# hs-32-spi.net
KiCad netlist of a schematic drawn in EAGLE
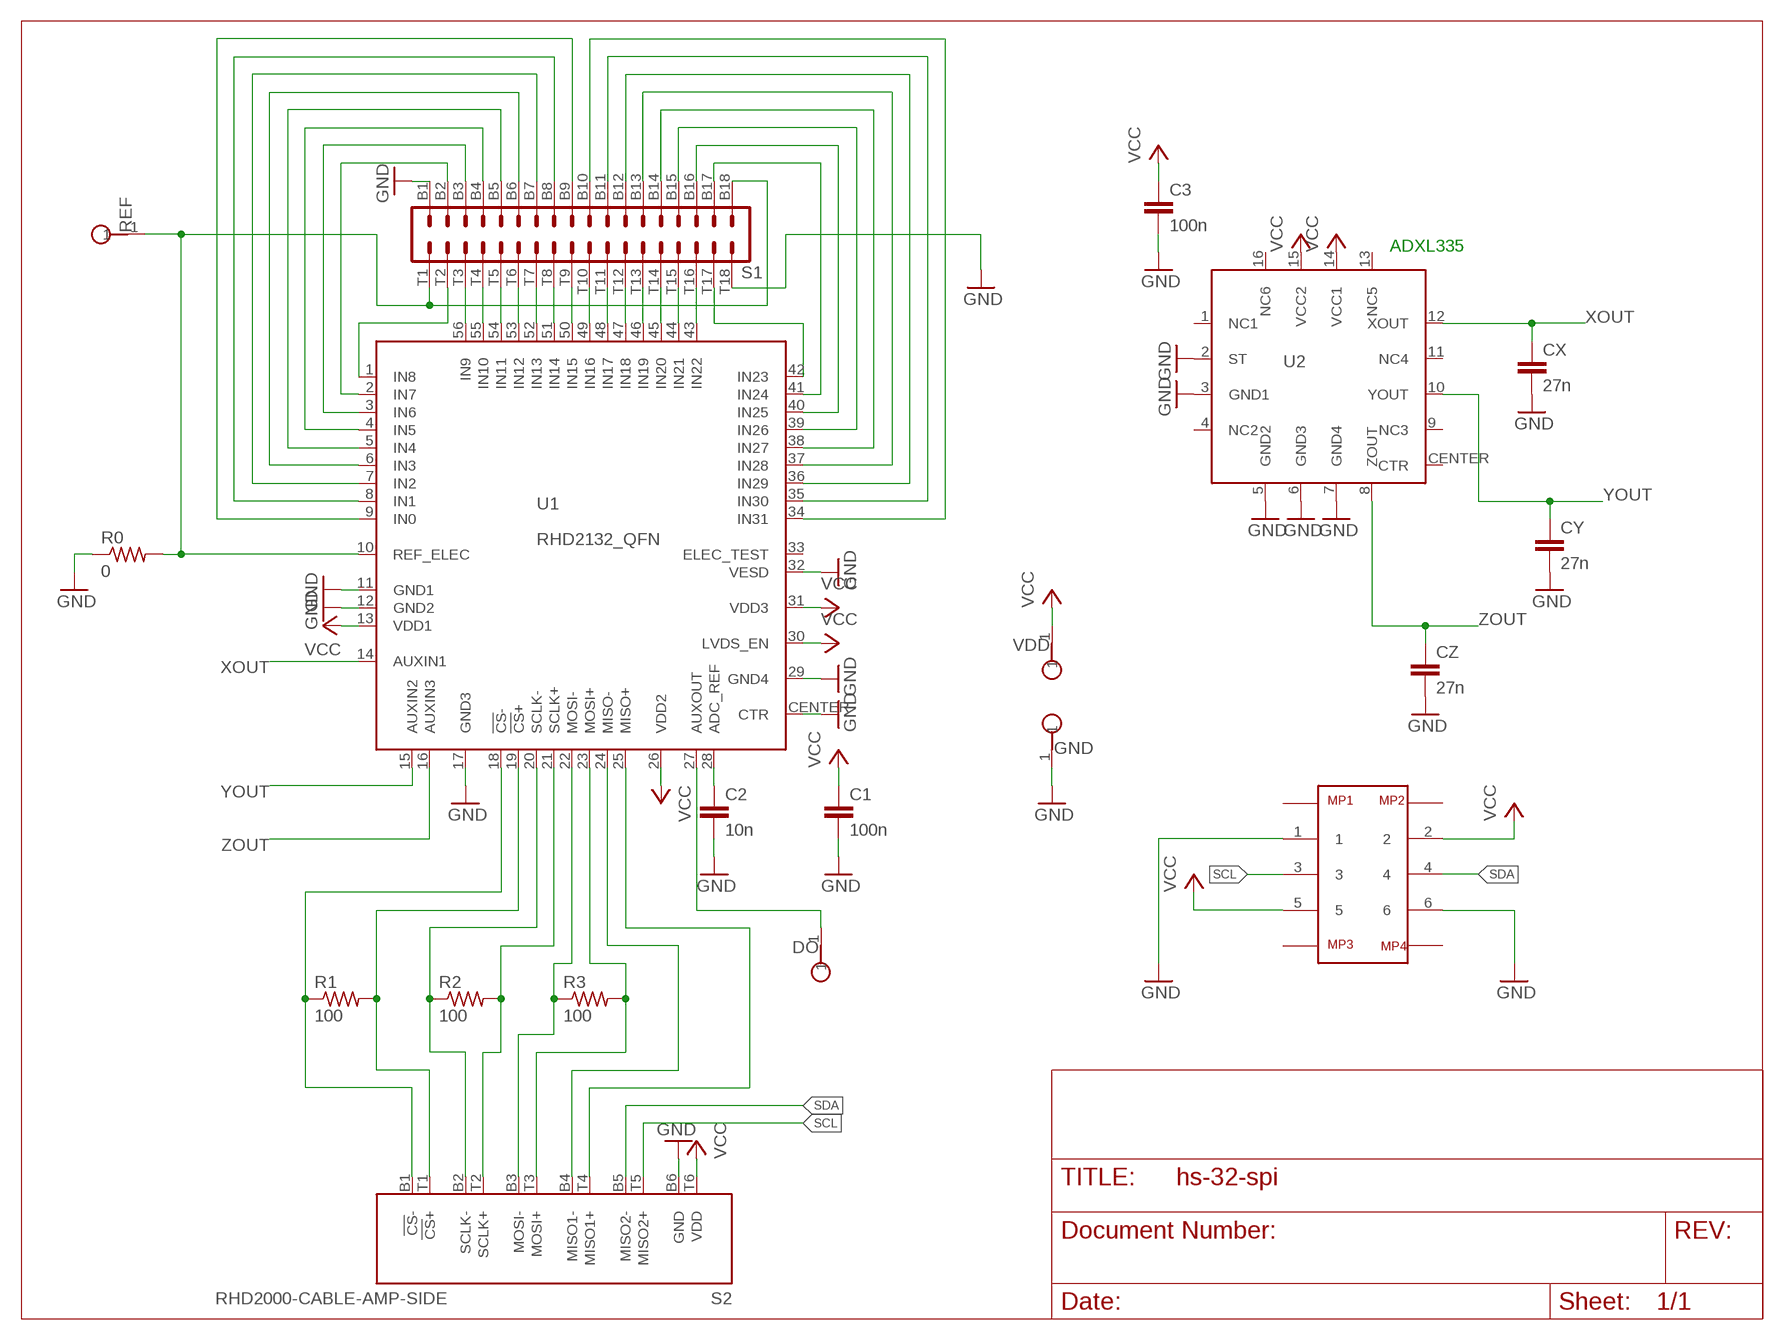
[diagram p0: schematic, sheet 1]

(export (version "E")
  (design (tool "Eeschema 10.0.6"))
  (components
    (comp (ref "C1")
      (value "100n")
      (footprint "eagle-import:0402")
      (libsource (lib "eagle-import") (part "C_0402"))
    )
    (comp (ref "C2")
      (value "10n")
      (footprint "eagle-import:0402")
      (libsource (lib "eagle-import") (part "C_0402"))
    )
    (comp (ref "C3")
      (value "100n")
      (footprint "eagle-import:0402")
      (libsource (lib "eagle-import") (part "C_0402"))
    )
    (comp (ref "CX")
      (value "27n")
      (footprint "eagle-import:0402")
      (libsource (lib "eagle-import") (part "C_0402"))
    )
    (comp (ref "CY")
      (value "27n")
      (footprint "eagle-import:0402")
      (libsource (lib "eagle-import") (part "C_0402"))
    )
    (comp (ref "CZ")
      (value "27n")
      (footprint "eagle-import:0402")
      (libsource (lib "eagle-import") (part "C_0402"))
    )
    (comp (ref "DO")
      (value "TESTPOINT_SMALL")
      (footprint "eagle-import:TESTPOINT_SMALL")
      (libsource (lib "eagle-import") (part "TESTPOINT_SMALL"))
    )
    (comp (ref "GND")
      (value "TESTPOINT_SMALL")
      (footprint "eagle-import:TESTPOINT_SMALL")
      (libsource (lib "eagle-import") (part "TESTPOINT_SMALL"))
    )
    (comp (ref "R0")
      (value "0")
      (footprint "eagle-import:0402")
      (libsource (lib "eagle-import") (part "R_0402"))
    )
    (comp (ref "R1")
      (value "100")
      (footprint "eagle-import:0201")
      (libsource (lib "eagle-import") (part "R_0201"))
    )
    (comp (ref "R2")
      (value "100")
      (footprint "eagle-import:0201")
      (libsource (lib "eagle-import") (part "R_0201"))
    )
    (comp (ref "R3")
      (value "100")
      (footprint "eagle-import:0201")
      (libsource (lib "eagle-import") (part "R_0201"))
    )
    (comp (ref "REF")
      (value "TESTPOINT_SMALL")
      (footprint "eagle-import:TESTPOINT_SMALL")
      (libsource (lib "eagle-import") (part "TESTPOINT_SMALL"))
    )
    (comp (ref "S1")
      (value "OMNETICS_A79025")
      (footprint "eagle-import:OMNETICS_A79025")
      (libsource (lib "eagle-import") (part "OMNETICS_A79025"))
    )
    (comp (ref "S2")
      (value "RHD2000-CABLE-AMP-SIDE")
      (footprint "eagle-import:OMNETICS_PZN-12-AA")
      (libsource (lib "eagle-import") (part "RHD2000-CABLE-AMP-SIDE"))
    )
    (comp (ref "U1")
      (value "RHD2132_QFN")
      (footprint "eagle-import:QFN56_8_X_8_LARGE")
      (libsource (lib "eagle-import") (part "RHD2132_QFN"))
    )
    (comp (ref "U2")
      (value "ADXL335")
      (footprint "eagle-import:ADXL335")
      (libsource (lib "eagle-import") (part "ADXL335"))
    )
    (comp (ref "U3")
      (value "MOLEX_5050700622")
      (footprint "eagle-import:MOLEX_5050700622")
      (libsource (lib "eagle-import") (part "MOLEX_5050700622"))
    )
    (comp (ref "VDD")
      (value "TESTPOINT_SMALL")
      (footprint "eagle-import:TESTPOINT_SMALL")
      (libsource (lib "eagle-import") (part "TESTPOINT_SMALL"))
    )
  )
  (nets
    (net (code "1") (name "/XOUT") (class "Default")
      (node (ref "CX") (pin "1") (pinfunction "1_1") (pintype "passive"))
      (node (ref "U1") (pin "14") (pinfunction "AUXIN1_14") (pintype "input"))
      (node (ref "U2") (pin "12") (pinfunction "XOUT_12") (pintype "output"))
    )
    (net (code "2") (name "/YOUT") (class "Default")
      (node (ref "CY") (pin "1") (pinfunction "1_1") (pintype "passive"))
      (node (ref "U1") (pin "15") (pinfunction "AUXIN2_15") (pintype "input"))
      (node (ref "U2") (pin "10") (pinfunction "YOUT_10") (pintype "output"))
    )
    (net (code "3") (name "/ZOUT") (class "Default")
      (node (ref "CZ") (pin "1") (pinfunction "1_1") (pintype "passive"))
      (node (ref "U1") (pin "16") (pinfunction "AUXIN3_16") (pintype "input"))
      (node (ref "U2") (pin "8") (pinfunction "ZOUT_8") (pintype "output"))
    )
    (net (code "4") (name "GND") (class "Default")
      (node (ref "C1") (pin "2") (pinfunction "2_2") (pintype "passive"))
      (node (ref "C2") (pin "2") (pinfunction "2_2") (pintype "passive"))
      (node (ref "C3") (pin "2") (pinfunction "2_2") (pintype "passive"))
      (node (ref "CX") (pin "2") (pinfunction "2_2") (pintype "passive"))
      (node (ref "CY") (pin "2") (pinfunction "2_2") (pintype "passive"))
      (node (ref "CZ") (pin "2") (pinfunction "2_2") (pintype "passive"))
      (node (ref "GND") (pin "1") (pinfunction "1_1") (pintype "passive"))
      (node (ref "R0") (pin "1") (pinfunction "1_1") (pintype "passive"))
      (node (ref "S1") (pin "B1") (pinfunction "B1_B1") (pintype "passive"))
      (node (ref "S1") (pin "T18") (pinfunction "T18_T18") (pintype "passive"))
      (node (ref "S2") (pin "B6") (pinfunction "GND_B6") (pintype "power_in"))
      (node (ref "U1") (pin "11") (pinfunction "GND1_11") (pintype "power_in"))
      (node (ref "U1") (pin "12") (pinfunction "GND2_12") (pintype "power_in"))
      (node (ref "U1") (pin "17") (pinfunction "GND3_17") (pintype "power_in"))
      (node (ref "U1") (pin "29") (pinfunction "GND4_29") (pintype "power_in"))
      (node (ref "U1") (pin "32") (pinfunction "VESD_32") (pintype "power_in"))
      (node (ref "U1") (pin "CENTER") (pinfunction "CTR_CENTER") (pintype "power_in"))
      (node (ref "U2") (pin "2") (pinfunction "ST_2") (pintype "input"))
      (node (ref "U2") (pin "3") (pinfunction "GND1_3") (pintype "power_in"))
      (node (ref "U2") (pin "5") (pinfunction "GND2_5") (pintype "power_in"))
      (node (ref "U2") (pin "6") (pinfunction "GND3_6") (pintype "power_in"))
      (node (ref "U2") (pin "7") (pinfunction "GND4_7") (pintype "power_in"))
      (node (ref "U3") (pin "1") (pinfunction "1_1") (pintype "bidirectional"))
      (node (ref "U3") (pin "6") (pinfunction "6_6") (pintype "bidirectional"))
    )
    (net (code "5") (name "Net-(S2-MISO1+)") (class "Default")
      (node (ref "S2") (pin "T4") (pinfunction "MISO1+_T4") (pintype "bidirectional"))
      (node (ref "U1") (pin "25") (pinfunction "MISO+_25") (pintype "output"))
    )
    (net (code "6") (name "Net-(S2-MISO1-)") (class "Default")
      (node (ref "S2") (pin "B4") (pinfunction "MISO1-_B4") (pintype "bidirectional"))
      (node (ref "U1") (pin "24") (pinfunction "MISO-_24") (pintype "output"))
    )
    (net (code "7") (name "Net-(S2-MOSI+)") (class "Default")
      (node (ref "R3") (pin "2") (pinfunction "2_2") (pintype "passive"))
      (node (ref "S2") (pin "T3") (pinfunction "MOSI+_T3") (pintype "bidirectional"))
      (node (ref "U1") (pin "23") (pinfunction "MOSI+_23") (pintype "input"))
    )
    (net (code "8") (name "Net-(S2-MOSI-)") (class "Default")
      (node (ref "R3") (pin "1") (pinfunction "1_1") (pintype "passive"))
      (node (ref "S2") (pin "B3") (pinfunction "MOSI-_B3") (pintype "bidirectional"))
      (node (ref "U1") (pin "22") (pinfunction "MOSI-_22") (pintype "input"))
    )
    (net (code "9") (name "Net-(S2-SCLK+)") (class "Default")
      (node (ref "R2") (pin "2") (pinfunction "2_2") (pintype "passive"))
      (node (ref "S2") (pin "T2") (pinfunction "SCLK+_T2") (pintype "bidirectional"))
      (node (ref "U1") (pin "21") (pinfunction "SCLK+_21") (pintype "input"))
    )
    (net (code "10") (name "Net-(S2-SCLK-)") (class "Default")
      (node (ref "R2") (pin "1") (pinfunction "1_1") (pintype "passive"))
      (node (ref "S2") (pin "B2") (pinfunction "SCLK-_B2") (pintype "bidirectional"))
      (node (ref "U1") (pin "20") (pinfunction "SCLK-_20") (pintype "input"))
    )
    (net (code "11") (name "Net-(S2-~{CS}+)") (class "Default")
      (node (ref "R1") (pin "2") (pinfunction "2_2") (pintype "passive"))
      (node (ref "S2") (pin "T1") (pinfunction "~{CS}+_T1") (pintype "bidirectional"))
      (node (ref "U1") (pin "19") (pinfunction "~{CS}+_19") (pintype "input"))
    )
    (net (code "12") (name "Net-(S2-~{CS}-)") (class "Default")
      (node (ref "R1") (pin "1") (pinfunction "1_1") (pintype "passive"))
      (node (ref "S2") (pin "B1") (pinfunction "~{CS}-_B1") (pintype "bidirectional"))
      (node (ref "U1") (pin "18") (pinfunction "~{CS}-_18") (pintype "input"))
    )
    (net (code "13") (name "Net-(U1-ADC_REF)") (class "Default")
      (node (ref "C2") (pin "1") (pinfunction "1_1") (pintype "passive"))
      (node (ref "U1") (pin "28") (pinfunction "ADC_REF_28") (pintype "passive"))
    )
    (net (code "14") (name "Net-(U1-AUXOUT)") (class "Default")
      (node (ref "DO") (pin "1") (pinfunction "1_1") (pintype "passive"))
      (node (ref "U1") (pin "27") (pinfunction "AUXOUT_27") (pintype "tri_state"))
    )
    (net (code "15") (name "Net-(U1-IN0)") (class "Default")
      (node (ref "S1") (pin "B9") (pinfunction "B9_B9") (pintype "passive"))
      (node (ref "U1") (pin "9") (pinfunction "IN0_9") (pintype "input"))
    )
    (net (code "16") (name "Net-(U1-IN1)") (class "Default")
      (node (ref "S1") (pin "B8") (pinfunction "B8_B8") (pintype "passive"))
      (node (ref "U1") (pin "8") (pinfunction "IN1_8") (pintype "input"))
    )
    (net (code "17") (name "Net-(U1-IN2)") (class "Default")
      (node (ref "S1") (pin "B7") (pinfunction "B7_B7") (pintype "passive"))
      (node (ref "U1") (pin "7") (pinfunction "IN2_7") (pintype "input"))
    )
    (net (code "18") (name "Net-(U1-IN3)") (class "Default")
      (node (ref "S1") (pin "B6") (pinfunction "B6_B6") (pintype "passive"))
      (node (ref "U1") (pin "6") (pinfunction "IN3_6") (pintype "input"))
    )
    (net (code "19") (name "Net-(U1-IN4)") (class "Default")
      (node (ref "S1") (pin "B5") (pinfunction "B5_B5") (pintype "passive"))
      (node (ref "U1") (pin "5") (pinfunction "IN4_5") (pintype "input"))
    )
    (net (code "20") (name "Net-(U1-IN5)") (class "Default")
      (node (ref "S1") (pin "B4") (pinfunction "B4_B4") (pintype "passive"))
      (node (ref "U1") (pin "4") (pinfunction "IN5_4") (pintype "input"))
    )
    (net (code "21") (name "Net-(U1-IN6)") (class "Default")
      (node (ref "S1") (pin "B3") (pinfunction "B3_B3") (pintype "passive"))
      (node (ref "U1") (pin "3") (pinfunction "IN6_3") (pintype "input"))
    )
    (net (code "22") (name "Net-(U1-IN7)") (class "Default")
      (node (ref "S1") (pin "B2") (pinfunction "B2_B2") (pintype "passive"))
      (node (ref "U1") (pin "2") (pinfunction "IN7_2") (pintype "input"))
    )
    (net (code "23") (name "Net-(U1-IN8)") (class "Default")
      (node (ref "S1") (pin "T2") (pinfunction "T2_T2") (pintype "passive"))
      (node (ref "U1") (pin "1") (pinfunction "IN8_1") (pintype "input"))
    )
    (net (code "24") (name "Net-(U1-IN9)") (class "Default")
      (node (ref "S1") (pin "T3") (pinfunction "T3_T3") (pintype "passive"))
      (node (ref "U1") (pin "56") (pinfunction "IN9_56") (pintype "input"))
    )
    (net (code "25") (name "Net-(U1-IN10)") (class "Default")
      (node (ref "S1") (pin "T4") (pinfunction "T4_T4") (pintype "passive"))
      (node (ref "U1") (pin "55") (pinfunction "IN10_55") (pintype "input"))
    )
    (net (code "26") (name "Net-(U1-IN11)") (class "Default")
      (node (ref "S1") (pin "T5") (pinfunction "T5_T5") (pintype "passive"))
      (node (ref "U1") (pin "54") (pinfunction "IN11_54") (pintype "input"))
    )
    (net (code "27") (name "Net-(U1-IN12)") (class "Default")
      (node (ref "S1") (pin "T6") (pinfunction "T6_T6") (pintype "passive"))
      (node (ref "U1") (pin "53") (pinfunction "IN12_53") (pintype "input"))
    )
    (net (code "28") (name "Net-(U1-IN13)") (class "Default")
      (node (ref "S1") (pin "T7") (pinfunction "T7_T7") (pintype "passive"))
      (node (ref "U1") (pin "52") (pinfunction "IN13_52") (pintype "input"))
    )
    (net (code "29") (name "Net-(U1-IN14)") (class "Default")
      (node (ref "S1") (pin "T8") (pinfunction "T8_T8") (pintype "passive"))
      (node (ref "U1") (pin "51") (pinfunction "IN14_51") (pintype "input"))
    )
    (net (code "30") (name "Net-(U1-IN15)") (class "Default")
      (node (ref "S1") (pin "T9") (pinfunction "T9_T9") (pintype "passive"))
      (node (ref "U1") (pin "50") (pinfunction "IN15_50") (pintype "input"))
    )
    (net (code "31") (name "Net-(U1-IN16)") (class "Default")
      (node (ref "S1") (pin "T10") (pinfunction "T10_T10") (pintype "passive"))
      (node (ref "U1") (pin "49") (pinfunction "IN16_49") (pintype "input"))
    )
    (net (code "32") (name "Net-(U1-IN17)") (class "Default")
      (node (ref "S1") (pin "T11") (pinfunction "T11_T11") (pintype "passive"))
      (node (ref "U1") (pin "48") (pinfunction "IN17_48") (pintype "input"))
    )
    (net (code "33") (name "Net-(U1-IN18)") (class "Default")
      (node (ref "S1") (pin "T12") (pinfunction "T12_T12") (pintype "passive"))
      (node (ref "U1") (pin "47") (pinfunction "IN18_47") (pintype "input"))
    )
    (net (code "34") (name "Net-(U1-IN19)") (class "Default")
      (node (ref "S1") (pin "T13") (pinfunction "T13_T13") (pintype "passive"))
      (node (ref "U1") (pin "46") (pinfunction "IN19_46") (pintype "input"))
    )
    (net (code "35") (name "Net-(U1-IN20)") (class "Default")
      (node (ref "S1") (pin "T14") (pinfunction "T14_T14") (pintype "passive"))
      (node (ref "U1") (pin "45") (pinfunction "IN20_45") (pintype "input"))
    )
    (net (code "36") (name "Net-(U1-IN21)") (class "Default")
      (node (ref "S1") (pin "T15") (pinfunction "T15_T15") (pintype "passive"))
      (node (ref "U1") (pin "44") (pinfunction "IN21_44") (pintype "input"))
    )
    (net (code "37") (name "Net-(U1-IN22)") (class "Default")
      (node (ref "S1") (pin "T16") (pinfunction "T16_T16") (pintype "passive"))
      (node (ref "U1") (pin "43") (pinfunction "IN22_43") (pintype "input"))
    )
    (net (code "38") (name "Net-(U1-IN23)") (class "Default")
      (node (ref "S1") (pin "T17") (pinfunction "T17_T17") (pintype "passive"))
      (node (ref "U1") (pin "42") (pinfunction "IN23_42") (pintype "input"))
    )
    (net (code "39") (name "Net-(U1-IN24)") (class "Default")
      (node (ref "S1") (pin "B17") (pinfunction "B17_B17") (pintype "passive"))
      (node (ref "U1") (pin "41") (pinfunction "IN24_41") (pintype "input"))
    )
    (net (code "40") (name "Net-(U1-IN25)") (class "Default")
      (node (ref "S1") (pin "B16") (pinfunction "B16_B16") (pintype "passive"))
      (node (ref "U1") (pin "40") (pinfunction "IN25_40") (pintype "input"))
    )
    (net (code "41") (name "Net-(U1-IN26)") (class "Default")
      (node (ref "S1") (pin "B15") (pinfunction "B15_B15") (pintype "passive"))
      (node (ref "U1") (pin "39") (pinfunction "IN26_39") (pintype "input"))
    )
    (net (code "42") (name "Net-(U1-IN27)") (class "Default")
      (node (ref "S1") (pin "B14") (pinfunction "B14_B14") (pintype "passive"))
      (node (ref "U1") (pin "38") (pinfunction "IN27_38") (pintype "input"))
    )
    (net (code "43") (name "Net-(U1-IN28)") (class "Default")
      (node (ref "S1") (pin "B13") (pinfunction "B13_B13") (pintype "passive"))
      (node (ref "U1") (pin "37") (pinfunction "IN28_37") (pintype "input"))
    )
    (net (code "44") (name "Net-(U1-IN29)") (class "Default")
      (node (ref "S1") (pin "B12") (pinfunction "B12_B12") (pintype "passive"))
      (node (ref "U1") (pin "36") (pinfunction "IN29_36") (pintype "input"))
    )
    (net (code "45") (name "Net-(U1-IN30)") (class "Default")
      (node (ref "S1") (pin "B11") (pinfunction "B11_B11") (pintype "passive"))
      (node (ref "U1") (pin "35") (pinfunction "IN30_35") (pintype "input"))
    )
    (net (code "46") (name "Net-(U1-IN31)") (class "Default")
      (node (ref "S1") (pin "B10") (pinfunction "B10_B10") (pintype "passive"))
      (node (ref "U1") (pin "34") (pinfunction "IN31_34") (pintype "input"))
    )
    (net (code "47") (name "Net-(U1-REF_ELEC)") (class "Default")
      (node (ref "R0") (pin "2") (pinfunction "2_2") (pintype "passive"))
      (node (ref "REF") (pin "1") (pinfunction "1_1") (pintype "passive"))
      (node (ref "S1") (pin "B18") (pinfunction "B18_B18") (pintype "passive"))
      (node (ref "S1") (pin "T1") (pinfunction "T1_T1") (pintype "passive"))
      (node (ref "U1") (pin "10") (pinfunction "REF_ELEC_10") (pintype "input"))
    )
    (net (code "48") (name "SCL") (class "Default")
      (node (ref "S2") (pin "T5") (pinfunction "MISO2+_T5") (pintype "bidirectional"))
      (node (ref "U3") (pin "3") (pinfunction "3_3") (pintype "bidirectional"))
    )
    (net (code "49") (name "SDA") (class "Default")
      (node (ref "S2") (pin "B5") (pinfunction "MISO2-_B5") (pintype "bidirectional"))
      (node (ref "U3") (pin "4") (pinfunction "4_4") (pintype "bidirectional"))
    )
    (net (code "50") (name "VCC") (class "Default")
      (node (ref "C1") (pin "1") (pinfunction "1_1") (pintype "passive"))
      (node (ref "C3") (pin "1") (pinfunction "1_1") (pintype "passive"))
      (node (ref "S2") (pin "T6") (pinfunction "VDD_T6") (pintype "bidirectional"))
      (node (ref "U1") (pin "13") (pinfunction "VDD1_13") (pintype "power_in"))
      (node (ref "U1") (pin "26") (pinfunction "VDD2_26") (pintype "power_in"))
      (node (ref "U1") (pin "30") (pinfunction "LVDS_EN_30") (pintype "input"))
      (node (ref "U1") (pin "31") (pinfunction "VDD3_31") (pintype "power_in"))
      (node (ref "U2") (pin "14") (pinfunction "VCC1_14") (pintype "power_in"))
      (node (ref "U2") (pin "15") (pinfunction "VCC2_15") (pintype "power_in"))
      (node (ref "U3") (pin "2") (pinfunction "2_2") (pintype "bidirectional"))
      (node (ref "U3") (pin "5") (pinfunction "5_5") (pintype "bidirectional"))
      (node (ref "VDD") (pin "1") (pinfunction "1_1") (pintype "passive"))
    )
    (net (code "51") (name "unconnected-(U1-ELEC_TEST-Pad33)") (class "Default")
      (node (ref "U1") (pin "33") (pinfunction "ELEC_TEST_33") (pintype "input"))
    )
    (net (code "52") (name "unconnected-(U2-CTR-PadCENTER)") (class "Default")
      (node (ref "U2") (pin "CENTER") (pinfunction "CTR_CENTER") (pintype "passive"))
    )
    (net (code "53") (name "unconnected-(U2-NC1-Pad1)") (class "Default")
      (node (ref "U2") (pin "1") (pinfunction "NC1_1") (pintype "no_connect"))
    )
    (net (code "54") (name "unconnected-(U2-NC2-Pad4)") (class "Default")
      (node (ref "U2") (pin "4") (pinfunction "NC2_4") (pintype "no_connect"))
    )
    (net (code "55") (name "unconnected-(U2-NC3-Pad9)") (class "Default")
      (node (ref "U2") (pin "9") (pinfunction "NC3_9") (pintype "no_connect"))
    )
    (net (code "56") (name "unconnected-(U2-NC4-Pad11)") (class "Default")
      (node (ref "U2") (pin "11") (pinfunction "NC4_11") (pintype "no_connect"))
    )
    (net (code "57") (name "unconnected-(U2-NC5-Pad13)") (class "Default")
      (node (ref "U2") (pin "13") (pinfunction "NC5_13") (pintype "no_connect"))
    )
    (net (code "58") (name "unconnected-(U2-NC6-Pad16)") (class "Default")
      (node (ref "U2") (pin "16") (pinfunction "NC6_16") (pintype "no_connect"))
    )
    (net (code "59") (name "unconnected-(U3-PadMP1)") (class "Default")
      (node (ref "U3") (pin "MP1") (pinfunction "MP1_MP1") (pintype "bidirectional"))
    )
    (net (code "60") (name "unconnected-(U3-PadMP2)") (class "Default")
      (node (ref "U3") (pin "MP2") (pinfunction "MP2_MP2") (pintype "bidirectional"))
    )
    (net (code "61") (name "unconnected-(U3-PadMP3)") (class "Default")
      (node (ref "U3") (pin "MP3") (pinfunction "MP3_MP3") (pintype "bidirectional"))
    )
    (net (code "62") (name "unconnected-(U3-PadMP4)") (class "Default")
      (node (ref "U3") (pin "MP4") (pinfunction "MP4_MP4") (pintype "bidirectional"))
    )
  )
)
